# SCK.net
KiCad netlist of a schematic drawn in EAGLE
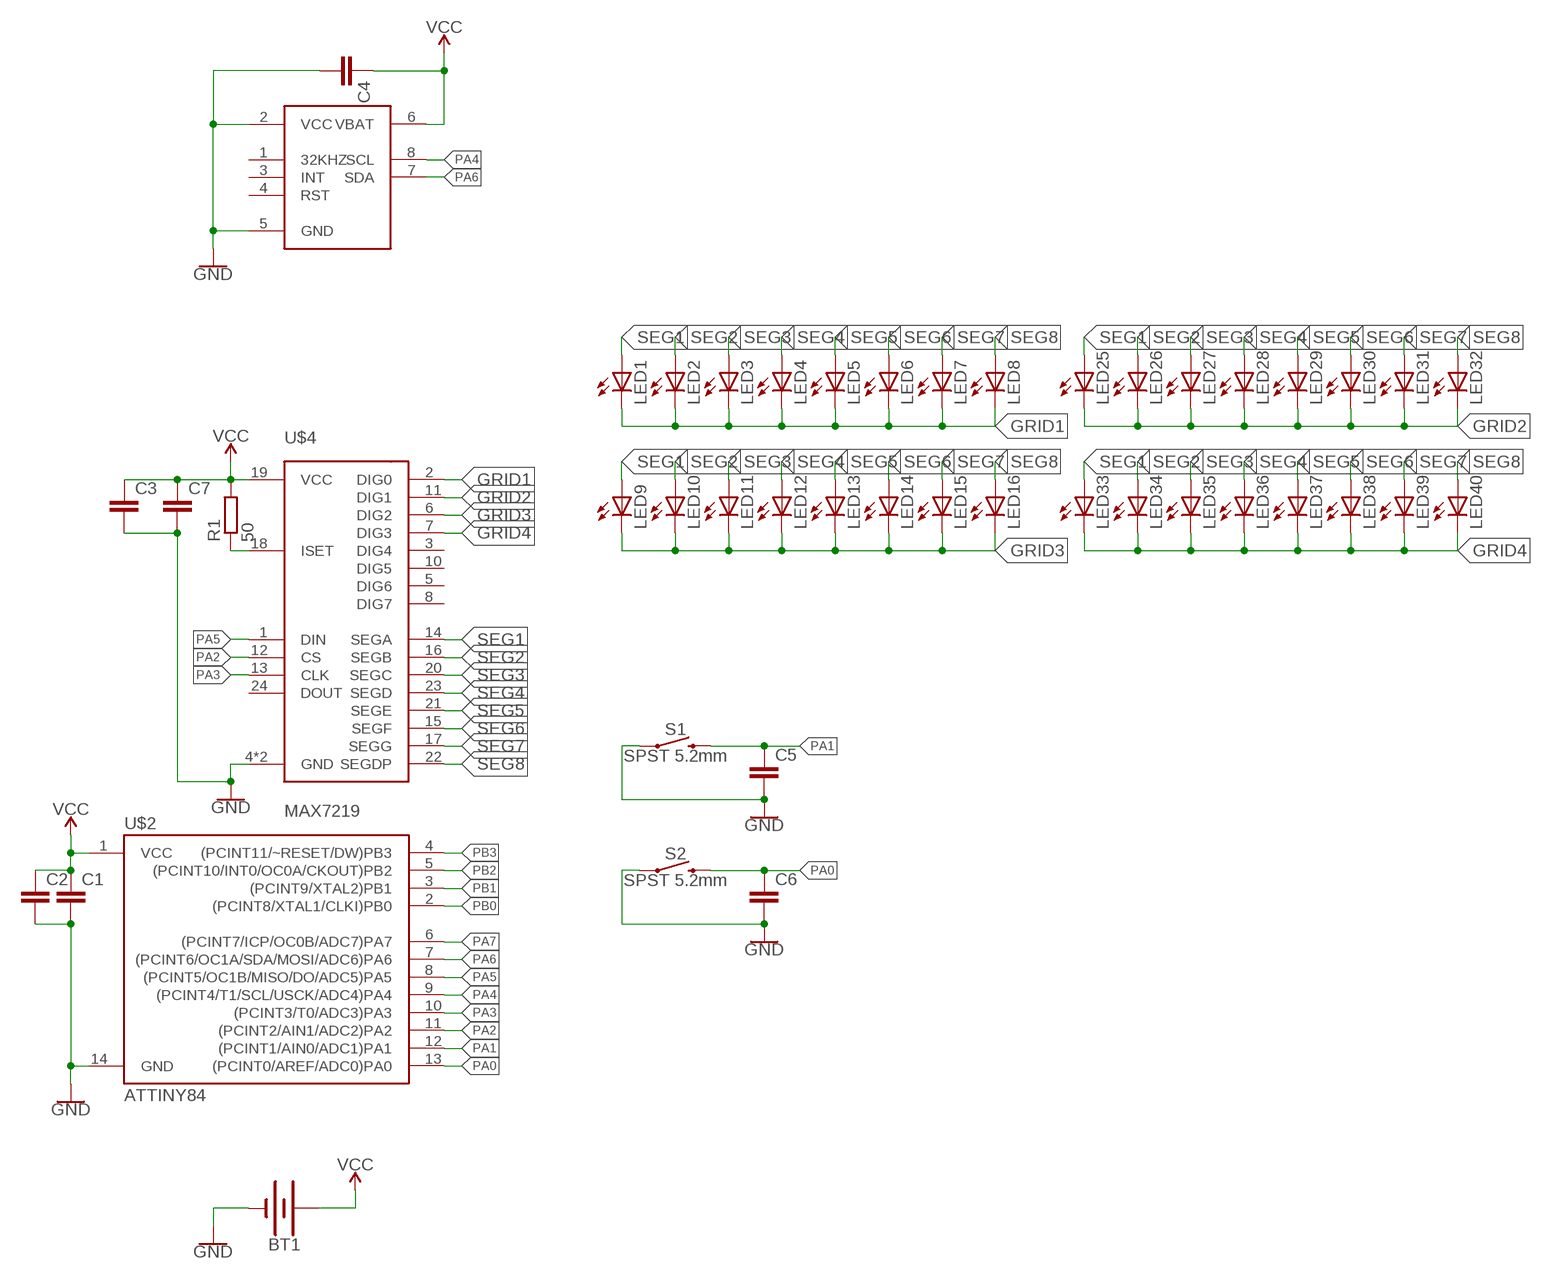
[diagram p0: schematic, sheet 1]

(export (version "E")
  (design (tool "Eeschema 10.0.6"))
  (components
    (comp (ref "BT1")
      (value "BATTERY-20MM_SMD_4LEGS")
      (footprint "eagle-import:BATTCON_20MM_4LEGS")
      (libsource (lib "eagle-import") (part "BATTERY-20MM_SMD_4LEGS"))
    )
    (comp (ref "C1")
      (value "C-EUC0805")
      (footprint "eagle-import:C0805")
      (libsource (lib "eagle-import") (part "C-EUC0805"))
    )
    (comp (ref "C2")
      (value "C-EUC0805")
      (footprint "eagle-import:C0805")
      (libsource (lib "eagle-import") (part "C-EUC0805"))
    )
    (comp (ref "C3")
      (value "C-EUC0805")
      (footprint "eagle-import:C0805")
      (libsource (lib "eagle-import") (part "C-EUC0805"))
    )
    (comp (ref "C4")
      (value "C-EUC0805")
      (footprint "eagle-import:C0805")
      (libsource (lib "eagle-import") (part "C-EUC0805"))
    )
    (comp (ref "C5")
      (value "C-EUC0805")
      (footprint "eagle-import:C0805")
      (libsource (lib "eagle-import") (part "C-EUC0805"))
    )
    (comp (ref "C6")
      (value "C-EUC0805")
      (footprint "eagle-import:C0805")
      (libsource (lib "eagle-import") (part "C-EUC0805"))
    )
    (comp (ref "C7")
      (value "C-EUC0805")
      (footprint "eagle-import:C0805")
      (libsource (lib "eagle-import") (part "C-EUC0805"))
    )
    (comp (ref "LED1")
      (value "LEDCHIPLED_0805")
      (footprint "eagle-import:CHIPLED_0805")
      (libsource (lib "eagle-import") (part "LEDCHIPLED_0805"))
    )
    (comp (ref "LED2")
      (value "LEDCHIPLED_0805")
      (footprint "eagle-import:CHIPLED_0805")
      (libsource (lib "eagle-import") (part "LEDCHIPLED_0805"))
    )
    (comp (ref "LED3")
      (value "LEDCHIPLED_0805")
      (footprint "eagle-import:CHIPLED_0805")
      (libsource (lib "eagle-import") (part "LEDCHIPLED_0805"))
    )
    (comp (ref "LED4")
      (value "LEDCHIPLED_0805")
      (footprint "eagle-import:CHIPLED_0805")
      (libsource (lib "eagle-import") (part "LEDCHIPLED_0805"))
    )
    (comp (ref "LED5")
      (value "LEDCHIPLED_0805")
      (footprint "eagle-import:CHIPLED_0805")
      (libsource (lib "eagle-import") (part "LEDCHIPLED_0805"))
    )
    (comp (ref "LED6")
      (value "LEDCHIPLED_0805")
      (footprint "eagle-import:CHIPLED_0805")
      (libsource (lib "eagle-import") (part "LEDCHIPLED_0805"))
    )
    (comp (ref "LED7")
      (value "LEDCHIPLED_0805")
      (footprint "eagle-import:CHIPLED_0805")
      (libsource (lib "eagle-import") (part "LEDCHIPLED_0805"))
    )
    (comp (ref "LED8")
      (value "LEDCHIPLED_0805")
      (footprint "eagle-import:CHIPLED_0805")
      (libsource (lib "eagle-import") (part "LEDCHIPLED_0805"))
    )
    (comp (ref "LED9")
      (value "LEDCHIPLED_0805")
      (footprint "eagle-import:CHIPLED_0805")
      (libsource (lib "eagle-import") (part "LEDCHIPLED_0805"))
    )
    (comp (ref "LED10")
      (value "LEDCHIPLED_0805")
      (footprint "eagle-import:CHIPLED_0805")
      (libsource (lib "eagle-import") (part "LEDCHIPLED_0805"))
    )
    (comp (ref "LED11")
      (value "LEDCHIPLED_0805")
      (footprint "eagle-import:CHIPLED_0805")
      (libsource (lib "eagle-import") (part "LEDCHIPLED_0805"))
    )
    (comp (ref "LED12")
      (value "LEDCHIPLED_0805")
      (footprint "eagle-import:CHIPLED_0805")
      (libsource (lib "eagle-import") (part "LEDCHIPLED_0805"))
    )
    (comp (ref "LED13")
      (value "LEDCHIPLED_0805")
      (footprint "eagle-import:CHIPLED_0805")
      (libsource (lib "eagle-import") (part "LEDCHIPLED_0805"))
    )
    (comp (ref "LED14")
      (value "LEDCHIPLED_0805")
      (footprint "eagle-import:CHIPLED_0805")
      (libsource (lib "eagle-import") (part "LEDCHIPLED_0805"))
    )
    (comp (ref "LED15")
      (value "LEDCHIPLED_0805")
      (footprint "eagle-import:CHIPLED_0805")
      (libsource (lib "eagle-import") (part "LEDCHIPLED_0805"))
    )
    (comp (ref "LED16")
      (value "LEDCHIPLED_0805")
      (footprint "eagle-import:CHIPLED_0805")
      (libsource (lib "eagle-import") (part "LEDCHIPLED_0805"))
    )
    (comp (ref "LED25")
      (value "LEDCHIPLED_0805")
      (footprint "eagle-import:CHIPLED_0805")
      (libsource (lib "eagle-import") (part "LEDCHIPLED_0805"))
    )
    (comp (ref "LED26")
      (value "LEDCHIPLED_0805")
      (footprint "eagle-import:CHIPLED_0805")
      (libsource (lib "eagle-import") (part "LEDCHIPLED_0805"))
    )
    (comp (ref "LED27")
      (value "LEDCHIPLED_0805")
      (footprint "eagle-import:CHIPLED_0805")
      (libsource (lib "eagle-import") (part "LEDCHIPLED_0805"))
    )
    (comp (ref "LED28")
      (value "LEDCHIPLED_0805")
      (footprint "eagle-import:CHIPLED_0805")
      (libsource (lib "eagle-import") (part "LEDCHIPLED_0805"))
    )
    (comp (ref "LED29")
      (value "LEDCHIPLED_0805")
      (footprint "eagle-import:CHIPLED_0805")
      (libsource (lib "eagle-import") (part "LEDCHIPLED_0805"))
    )
    (comp (ref "LED30")
      (value "LEDCHIPLED_0805")
      (footprint "eagle-import:CHIPLED_0805")
      (libsource (lib "eagle-import") (part "LEDCHIPLED_0805"))
    )
    (comp (ref "LED31")
      (value "LEDCHIPLED_0805")
      (footprint "eagle-import:CHIPLED_0805")
      (libsource (lib "eagle-import") (part "LEDCHIPLED_0805"))
    )
    (comp (ref "LED32")
      (value "LEDCHIPLED_0805")
      (footprint "eagle-import:CHIPLED_0805")
      (libsource (lib "eagle-import") (part "LEDCHIPLED_0805"))
    )
    (comp (ref "LED33")
      (value "LEDCHIPLED_0805")
      (footprint "eagle-import:CHIPLED_0805")
      (libsource (lib "eagle-import") (part "LEDCHIPLED_0805"))
    )
    (comp (ref "LED34")
      (value "LEDCHIPLED_0805")
      (footprint "eagle-import:CHIPLED_0805")
      (libsource (lib "eagle-import") (part "LEDCHIPLED_0805"))
    )
    (comp (ref "LED35")
      (value "LEDCHIPLED_0805")
      (footprint "eagle-import:CHIPLED_0805")
      (libsource (lib "eagle-import") (part "LEDCHIPLED_0805"))
    )
    (comp (ref "LED36")
      (value "LEDCHIPLED_0805")
      (footprint "eagle-import:CHIPLED_0805")
      (libsource (lib "eagle-import") (part "LEDCHIPLED_0805"))
    )
    (comp (ref "LED37")
      (value "LEDCHIPLED_0805")
      (footprint "eagle-import:CHIPLED_0805")
      (libsource (lib "eagle-import") (part "LEDCHIPLED_0805"))
    )
    (comp (ref "LED38")
      (value "LEDCHIPLED_0805")
      (footprint "eagle-import:CHIPLED_0805")
      (libsource (lib "eagle-import") (part "LEDCHIPLED_0805"))
    )
    (comp (ref "LED39")
      (value "LEDCHIPLED_0805")
      (footprint "eagle-import:CHIPLED_0805")
      (libsource (lib "eagle-import") (part "LEDCHIPLED_0805"))
    )
    (comp (ref "LED40")
      (value "LEDCHIPLED_0805")
      (footprint "eagle-import:CHIPLED_0805")
      (libsource (lib "eagle-import") (part "LEDCHIPLED_0805"))
    )
    (comp (ref "R1")
      (value "50")
      (footprint "eagle-import:R0805")
      (libsource (lib "eagle-import") (part "R-EU_R0805"))
    )
    (comp (ref "S1")
      (value "SPST 5.2mm")
      (footprint "eagle-import:TACTILE_SWITCH_SMD_4.6X2.8MM")
      (libsource (lib "eagle-import") (part "MOMENTARY-SWITCH-SPST-SMD-4.6X2.8MM"))
    )
    (comp (ref "S2")
      (value "SPST 5.2mm")
      (footprint "eagle-import:TACTILE_SWITCH_SMD_4.6X2.8MM")
      (libsource (lib "eagle-import") (part "MOMENTARY-SWITCH-SPST-SMD-4.6X2.8MM"))
    )
    (comp (ref "U$2")
      (value "ATTINY84")
      (footprint "eagle-import:SOIC127P599X175-14")
      (libsource (lib "eagle-import") (part "ATTINY84"))
    )
    (comp (ref "U$3")
      (value "DS3231M")
      (footprint "eagle-import:SOIC127P600X175-8")
      (libsource (lib "eagle-import") (part "DS3231M"))
    )
    (comp (ref "U$4")
      (value "MAX7219")
      (footprint "eagle-import:SOIC127P1032X265-24")
      (libsource (lib "eagle-import") (part "MAX7219"))
    )
  )
  (nets
    (net (code "1") (name "GND") (class "Default")
      (node (ref "BT1") (pin "NEGATIVE") (pinfunction "-_NEGATIVE") (pintype "power_in"))
      (node (ref "C1") (pin "2") (pinfunction "2_2") (pintype "passive"))
      (node (ref "C2") (pin "2") (pinfunction "2_2") (pintype "passive"))
      (node (ref "C3") (pin "2") (pinfunction "2_2") (pintype "passive"))
      (node (ref "C4") (pin "2") (pinfunction "2_2") (pintype "passive"))
      (node (ref "C5") (pin "2") (pinfunction "2_2") (pintype "passive"))
      (node (ref "C6") (pin "2") (pinfunction "2_2") (pintype "passive"))
      (node (ref "C7") (pin "2") (pinfunction "2_2") (pintype "passive"))
      (node (ref "S1") (pin "1") (pinfunction "1_1") (pintype "passive"))
      (node (ref "S1") (pin "2") (pinfunction "1_2") (pintype "passive"))
      (node (ref "S2") (pin "1") (pinfunction "1_1") (pintype "passive"))
      (node (ref "S2") (pin "2") (pinfunction "1_2") (pintype "passive"))
      (node (ref "U$2") (pin "14") (pinfunction "GND_14") (pintype "bidirectional"))
      (node (ref "U$3") (pin "2") (pinfunction "VCC_2") (pintype "power_in"))
      (node (ref "U$3") (pin "5") (pinfunction "GND_5") (pintype "power_in"))
      (node (ref "U$4") (pin "4") (pinfunction "GND_4") (pintype "power_in"))
      (node (ref "U$4") (pin "9") (pinfunction "GND_9") (pintype "power_in"))
    )
    (net (code "2") (name "GRID1") (class "Default")
      (node (ref "LED1") (pin "C") (pinfunction "C_C") (pintype "passive"))
      (node (ref "LED2") (pin "C") (pinfunction "C_C") (pintype "passive"))
      (node (ref "LED3") (pin "C") (pinfunction "C_C") (pintype "passive"))
      (node (ref "LED4") (pin "C") (pinfunction "C_C") (pintype "passive"))
      (node (ref "LED5") (pin "C") (pinfunction "C_C") (pintype "passive"))
      (node (ref "LED6") (pin "C") (pinfunction "C_C") (pintype "passive"))
      (node (ref "LED7") (pin "C") (pinfunction "C_C") (pintype "passive"))
      (node (ref "LED8") (pin "C") (pinfunction "C_C") (pintype "passive"))
      (node (ref "U$4") (pin "2") (pinfunction "DIG0_2") (pintype "output"))
    )
    (net (code "3") (name "GRID2") (class "Default")
      (node (ref "LED25") (pin "C") (pinfunction "C_C") (pintype "passive"))
      (node (ref "LED26") (pin "C") (pinfunction "C_C") (pintype "passive"))
      (node (ref "LED27") (pin "C") (pinfunction "C_C") (pintype "passive"))
      (node (ref "LED28") (pin "C") (pinfunction "C_C") (pintype "passive"))
      (node (ref "LED29") (pin "C") (pinfunction "C_C") (pintype "passive"))
      (node (ref "LED30") (pin "C") (pinfunction "C_C") (pintype "passive"))
      (node (ref "LED31") (pin "C") (pinfunction "C_C") (pintype "passive"))
      (node (ref "LED32") (pin "C") (pinfunction "C_C") (pintype "passive"))
      (node (ref "U$4") (pin "11") (pinfunction "DIG1_11") (pintype "output"))
    )
    (net (code "4") (name "GRID3") (class "Default")
      (node (ref "LED10") (pin "C") (pinfunction "C_C") (pintype "passive"))
      (node (ref "LED11") (pin "C") (pinfunction "C_C") (pintype "passive"))
      (node (ref "LED12") (pin "C") (pinfunction "C_C") (pintype "passive"))
      (node (ref "LED13") (pin "C") (pinfunction "C_C") (pintype "passive"))
      (node (ref "LED14") (pin "C") (pinfunction "C_C") (pintype "passive"))
      (node (ref "LED15") (pin "C") (pinfunction "C_C") (pintype "passive"))
      (node (ref "LED16") (pin "C") (pinfunction "C_C") (pintype "passive"))
      (node (ref "LED9") (pin "C") (pinfunction "C_C") (pintype "passive"))
      (node (ref "U$4") (pin "6") (pinfunction "DIG2_6") (pintype "output"))
    )
    (net (code "5") (name "GRID4") (class "Default")
      (node (ref "LED33") (pin "C") (pinfunction "C_C") (pintype "passive"))
      (node (ref "LED34") (pin "C") (pinfunction "C_C") (pintype "passive"))
      (node (ref "LED35") (pin "C") (pinfunction "C_C") (pintype "passive"))
      (node (ref "LED36") (pin "C") (pinfunction "C_C") (pintype "passive"))
      (node (ref "LED37") (pin "C") (pinfunction "C_C") (pintype "passive"))
      (node (ref "LED38") (pin "C") (pinfunction "C_C") (pintype "passive"))
      (node (ref "LED39") (pin "C") (pinfunction "C_C") (pintype "passive"))
      (node (ref "LED40") (pin "C") (pinfunction "C_C") (pintype "passive"))
      (node (ref "U$4") (pin "7") (pinfunction "DIG3_7") (pintype "output"))
    )
    (net (code "6") (name "Net-(U$4-ISET)") (class "Default")
      (node (ref "R1") (pin "1") (pinfunction "1_1") (pintype "passive"))
      (node (ref "U$4") (pin "18") (pinfunction "ISET_18") (pintype "input"))
    )
    (net (code "7") (name "PA0") (class "Default")
      (node (ref "C6") (pin "1") (pinfunction "1_1") (pintype "passive"))
      (node (ref "S2") (pin "3") (pinfunction "2_3") (pintype "passive"))
      (node (ref "S2") (pin "4") (pinfunction "2_4") (pintype "passive"))
      (node (ref "U$2") (pin "13") (pinfunction "(PCINT0/AREF/ADC0)PA0_13") (pintype "bidirectional"))
    )
    (net (code "8") (name "PA1") (class "Default")
      (node (ref "C5") (pin "1") (pinfunction "1_1") (pintype "passive"))
      (node (ref "S1") (pin "3") (pinfunction "2_3") (pintype "passive"))
      (node (ref "S1") (pin "4") (pinfunction "2_4") (pintype "passive"))
      (node (ref "U$2") (pin "12") (pinfunction "(PCINT1/AIN0/ADC1)PA1_12") (pintype "bidirectional"))
    )
    (net (code "9") (name "PA2") (class "Default")
      (node (ref "U$2") (pin "11") (pinfunction "(PCINT2/AIN1/ADC2)PA2_11") (pintype "bidirectional"))
      (node (ref "U$4") (pin "12") (pinfunction "CS_12") (pintype "input"))
    )
    (net (code "10") (name "PA3") (class "Default")
      (node (ref "U$2") (pin "10") (pinfunction "(PCINT3/T0/ADC3)PA3_10") (pintype "bidirectional"))
      (node (ref "U$4") (pin "13") (pinfunction "CLK_13") (pintype "input"))
    )
    (net (code "11") (name "PA4") (class "Default")
      (node (ref "U$2") (pin "9") (pinfunction "(PCINT4/T1/SCL/USCK/ADC4)PA4_9") (pintype "bidirectional"))
      (node (ref "U$3") (pin "8") (pinfunction "SCL_8") (pintype "bidirectional"))
    )
    (net (code "12") (name "PA5") (class "Default")
      (node (ref "U$2") (pin "8") (pinfunction "(PCINT5/OC1B/MISO/DO/ADC5)PA5_8") (pintype "bidirectional"))
      (node (ref "U$4") (pin "1") (pinfunction "DIN_1") (pintype "input"))
    )
    (net (code "13") (name "PA6") (class "Default")
      (node (ref "U$2") (pin "7") (pinfunction "(PCINT6/OC1A/SDA/MOSI/ADC6)PA6_7") (pintype "bidirectional"))
      (node (ref "U$3") (pin "7") (pinfunction "SDA_7") (pintype "bidirectional"))
    )
    (net (code "14") (name "PA7") (class "Default")
      (node (ref "U$2") (pin "6") (pinfunction "(PCINT7/ICP/OC0B/ADC7)PA7_6") (pintype "bidirectional"))
    )
    (net (code "15") (name "PB0") (class "Default")
      (node (ref "U$2") (pin "2") (pinfunction "(PCINT8/XTAL1/CLKI)PB0_2") (pintype "bidirectional"))
    )
    (net (code "16") (name "PB1") (class "Default")
      (node (ref "U$2") (pin "3") (pinfunction "(PCINT9/XTAL2)PB1_3") (pintype "bidirectional"))
    )
    (net (code "17") (name "PB2") (class "Default")
      (node (ref "U$2") (pin "5") (pinfunction "(PCINT10/INT0/OC0A/CKOUT)PB2_5") (pintype "bidirectional"))
    )
    (net (code "18") (name "PB3") (class "Default")
      (node (ref "U$2") (pin "4") (pinfunction "(PCINT11/~{RESET/DW})PB3_4") (pintype "bidirectional"))
    )
    (net (code "19") (name "SEG1") (class "Default")
      (node (ref "LED1") (pin "A") (pinfunction "A_A") (pintype "passive"))
      (node (ref "LED25") (pin "A") (pinfunction "A_A") (pintype "passive"))
      (node (ref "LED33") (pin "A") (pinfunction "A_A") (pintype "passive"))
      (node (ref "LED9") (pin "A") (pinfunction "A_A") (pintype "passive"))
      (node (ref "U$4") (pin "14") (pinfunction "SEGA_14") (pintype "output"))
    )
    (net (code "20") (name "SEG2") (class "Default")
      (node (ref "LED10") (pin "A") (pinfunction "A_A") (pintype "passive"))
      (node (ref "LED2") (pin "A") (pinfunction "A_A") (pintype "passive"))
      (node (ref "LED26") (pin "A") (pinfunction "A_A") (pintype "passive"))
      (node (ref "LED34") (pin "A") (pinfunction "A_A") (pintype "passive"))
      (node (ref "U$4") (pin "16") (pinfunction "SEGB_16") (pintype "output"))
    )
    (net (code "21") (name "SEG3") (class "Default")
      (node (ref "LED11") (pin "A") (pinfunction "A_A") (pintype "passive"))
      (node (ref "LED27") (pin "A") (pinfunction "A_A") (pintype "passive"))
      (node (ref "LED3") (pin "A") (pinfunction "A_A") (pintype "passive"))
      (node (ref "LED35") (pin "A") (pinfunction "A_A") (pintype "passive"))
      (node (ref "U$4") (pin "20") (pinfunction "SEGC_20") (pintype "output"))
    )
    (net (code "22") (name "SEG4") (class "Default")
      (node (ref "LED12") (pin "A") (pinfunction "A_A") (pintype "passive"))
      (node (ref "LED28") (pin "A") (pinfunction "A_A") (pintype "passive"))
      (node (ref "LED36") (pin "A") (pinfunction "A_A") (pintype "passive"))
      (node (ref "LED4") (pin "A") (pinfunction "A_A") (pintype "passive"))
      (node (ref "U$4") (pin "23") (pinfunction "SEGD_23") (pintype "output"))
    )
    (net (code "23") (name "SEG5") (class "Default")
      (node (ref "LED13") (pin "A") (pinfunction "A_A") (pintype "passive"))
      (node (ref "LED29") (pin "A") (pinfunction "A_A") (pintype "passive"))
      (node (ref "LED37") (pin "A") (pinfunction "A_A") (pintype "passive"))
      (node (ref "LED5") (pin "A") (pinfunction "A_A") (pintype "passive"))
      (node (ref "U$4") (pin "21") (pinfunction "SEGE_21") (pintype "output"))
    )
    (net (code "24") (name "SEG6") (class "Default")
      (node (ref "LED14") (pin "A") (pinfunction "A_A") (pintype "passive"))
      (node (ref "LED30") (pin "A") (pinfunction "A_A") (pintype "passive"))
      (node (ref "LED38") (pin "A") (pinfunction "A_A") (pintype "passive"))
      (node (ref "LED6") (pin "A") (pinfunction "A_A") (pintype "passive"))
      (node (ref "U$4") (pin "15") (pinfunction "SEGF_15") (pintype "output"))
    )
    (net (code "25") (name "SEG7") (class "Default")
      (node (ref "LED15") (pin "A") (pinfunction "A_A") (pintype "passive"))
      (node (ref "LED31") (pin "A") (pinfunction "A_A") (pintype "passive"))
      (node (ref "LED39") (pin "A") (pinfunction "A_A") (pintype "passive"))
      (node (ref "LED7") (pin "A") (pinfunction "A_A") (pintype "passive"))
      (node (ref "U$4") (pin "17") (pinfunction "SEGG_17") (pintype "output"))
    )
    (net (code "26") (name "SEG8") (class "Default")
      (node (ref "LED16") (pin "A") (pinfunction "A_A") (pintype "passive"))
      (node (ref "LED32") (pin "A") (pinfunction "A_A") (pintype "passive"))
      (node (ref "LED40") (pin "A") (pinfunction "A_A") (pintype "passive"))
      (node (ref "LED8") (pin "A") (pinfunction "A_A") (pintype "passive"))
      (node (ref "U$4") (pin "22") (pinfunction "SEGDP_22") (pintype "output"))
    )
    (net (code "27") (name "VCC") (class "Default")
      (node (ref "BT1") (pin "POSITIVE@1") (pinfunction "+_POSITIVE@1") (pintype "power_in"))
      (node (ref "BT1") (pin "POSITIVE@2") (pinfunction "+_POSITIVE@2") (pintype "power_in"))
      (node (ref "BT1") (pin "POSITIVE@3") (pinfunction "+_POSITIVE@3") (pintype "power_in"))
      (node (ref "BT1") (pin "POSITIVE@4") (pinfunction "+_POSITIVE@4") (pintype "power_in"))
      (node (ref "C1") (pin "1") (pinfunction "1_1") (pintype "passive"))
      (node (ref "C2") (pin "1") (pinfunction "1_1") (pintype "passive"))
      (node (ref "C3") (pin "1") (pinfunction "1_1") (pintype "passive"))
      (node (ref "C4") (pin "1") (pinfunction "1_1") (pintype "passive"))
      (node (ref "C7") (pin "1") (pinfunction "1_1") (pintype "passive"))
      (node (ref "R1") (pin "2") (pinfunction "2_2") (pintype "passive"))
      (node (ref "U$2") (pin "1") (pinfunction "VCC_1") (pintype "bidirectional"))
      (node (ref "U$3") (pin "6") (pinfunction "VBAT_6") (pintype "power_in"))
      (node (ref "U$4") (pin "19") (pinfunction "VCC_19") (pintype "power_in"))
    )
    (net (code "28") (name "unconnected-(U$3-32KHZ-Pad1)") (class "Default")
      (node (ref "U$3") (pin "1") (pinfunction "32KHZ_1") (pintype "bidirectional"))
    )
    (net (code "29") (name "unconnected-(U$3-INT-Pad3)") (class "Default")
      (node (ref "U$3") (pin "3") (pinfunction "INT_3") (pintype "bidirectional"))
    )
    (net (code "30") (name "unconnected-(U$3-RST-Pad4)") (class "Default")
      (node (ref "U$3") (pin "4") (pinfunction "RST_4") (pintype "bidirectional"))
    )
    (net (code "31") (name "unconnected-(U$4-DIG4-Pad3)") (class "Default")
      (node (ref "U$4") (pin "3") (pinfunction "DIG4_3") (pintype "output"))
    )
    (net (code "32") (name "unconnected-(U$4-DIG5-Pad10)") (class "Default")
      (node (ref "U$4") (pin "10") (pinfunction "DIG5_10") (pintype "output"))
    )
    (net (code "33") (name "unconnected-(U$4-DIG6-Pad5)") (class "Default")
      (node (ref "U$4") (pin "5") (pinfunction "DIG6_5") (pintype "output"))
    )
    (net (code "34") (name "unconnected-(U$4-DIG7-Pad8)") (class "Default")
      (node (ref "U$4") (pin "8") (pinfunction "DIG7_8") (pintype "output"))
    )
    (net (code "35") (name "unconnected-(U$4-DOUT-Pad24)") (class "Default")
      (node (ref "U$4") (pin "24") (pinfunction "DOUT_24") (pintype "output"))
    )
  )
)
